# GF_Logo_PCB.net
KiCad netlist of a schematic drawn in EAGLE
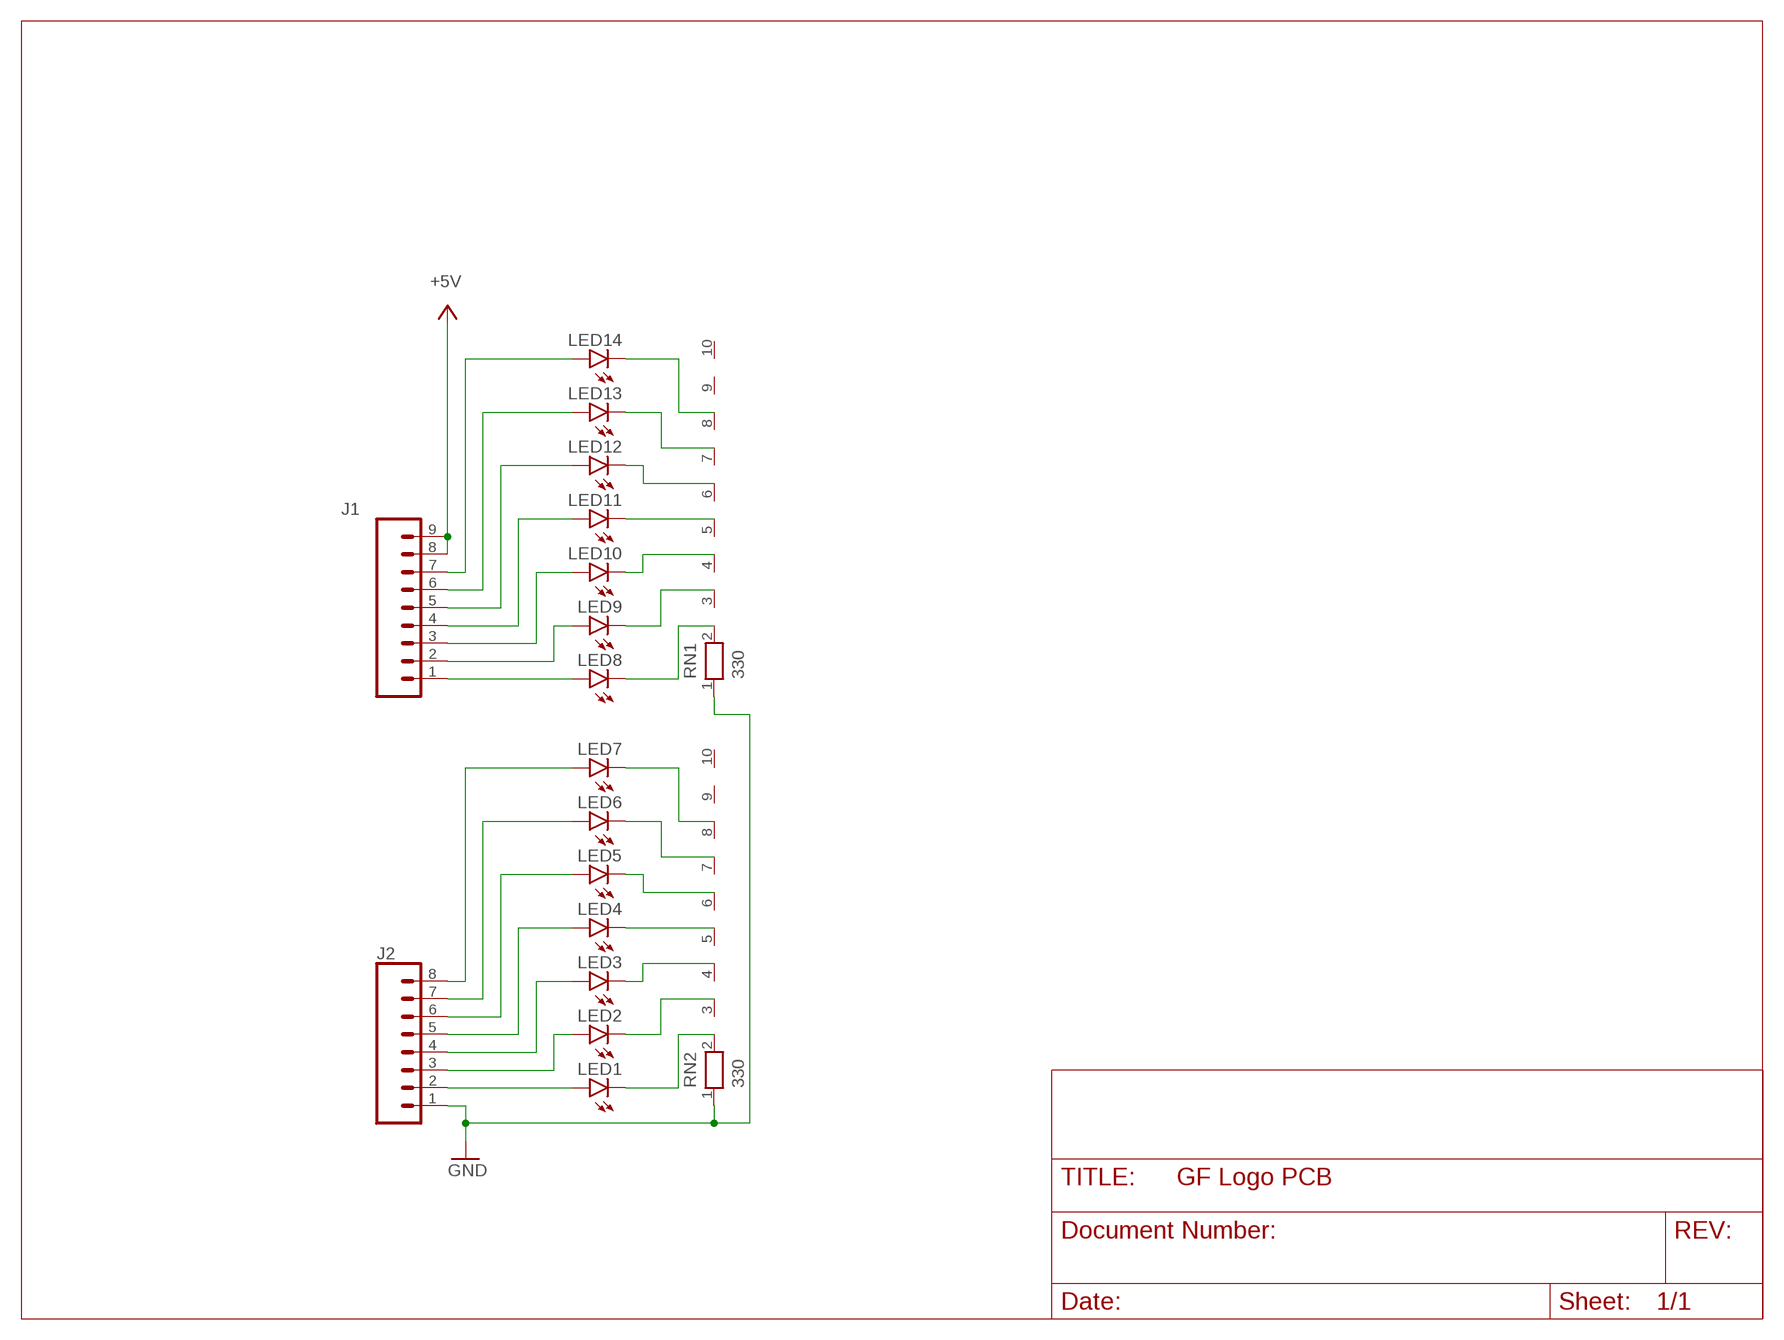
[diagram p0: schematic, sheet 1]

(export (version "E")
  (design (tool "Eeschema 10.0.6"))
  (components
    (comp (ref "J1")
      (value "CONN_09")
      (footprint "eagle-import:1X09")
      (libsource (lib "eagle-import") (part "CONN_09"))
    )
    (comp (ref "J2")
      (value "CONN_08\"")
      (footprint "eagle-import:1X08")
      (libsource (lib "eagle-import") (part "CONN_08{dblquote}"))
    )
    (comp (ref "LED1")
      (value "Grn")
      (footprint "eagle-import:LED3MM")
      (libsource (lib "eagle-import") (part "LED3MM"))
    )
    (comp (ref "LED2")
      (value "Grn")
      (footprint "eagle-import:LED3MM")
      (libsource (lib "eagle-import") (part "LED3MM"))
    )
    (comp (ref "LED3")
      (value "Grn")
      (footprint "eagle-import:LED3MM")
      (libsource (lib "eagle-import") (part "LED3MM"))
    )
    (comp (ref "LED4")
      (value "Grn")
      (footprint "eagle-import:LED3MM")
      (libsource (lib "eagle-import") (part "LED3MM"))
    )
    (comp (ref "LED5")
      (value "Grn")
      (footprint "eagle-import:LED3MM")
      (libsource (lib "eagle-import") (part "LED3MM"))
    )
    (comp (ref "LED6")
      (value "Grn")
      (footprint "eagle-import:LED3MM")
      (libsource (lib "eagle-import") (part "LED3MM"))
    )
    (comp (ref "LED7")
      (value "Grn")
      (footprint "eagle-import:LED3MM")
      (libsource (lib "eagle-import") (part "LED3MM"))
    )
    (comp (ref "LED8")
      (value "Grn")
      (footprint "eagle-import:LED3MM")
      (libsource (lib "eagle-import") (part "LED3MM"))
    )
    (comp (ref "LED9")
      (value "Grn")
      (footprint "eagle-import:LED3MM")
      (libsource (lib "eagle-import") (part "LED3MM"))
    )
    (comp (ref "LED10")
      (value "Grn")
      (footprint "eagle-import:LED3MM")
      (libsource (lib "eagle-import") (part "LED3MM"))
    )
    (comp (ref "LED11")
      (value "Grn")
      (footprint "eagle-import:LED3MM")
      (libsource (lib "eagle-import") (part "LED3MM"))
    )
    (comp (ref "LED12")
      (value "Grn")
      (footprint "eagle-import:LED3MM")
      (libsource (lib "eagle-import") (part "LED3MM"))
    )
    (comp (ref "LED13")
      (value "Grn")
      (footprint "eagle-import:LED3MM")
      (libsource (lib "eagle-import") (part "LED3MM"))
    )
    (comp (ref "LED14")
      (value "Grn")
      (footprint "eagle-import:LED3MM")
      (libsource (lib "eagle-import") (part "LED3MM"))
    )
    (comp (ref "RN1")
      (value "330")
      (footprint "eagle-import:RN-10")
      (libsource (lib "eagle-import") (part "RN09"))
    )
    (comp (ref "RN2")
      (value "330")
      (footprint "eagle-import:RN-10")
      (libsource (lib "eagle-import") (part "RN09"))
    )
  )
  (nets
    (net (code "1") (name "+5V") (class "Default")
      (node (ref "J1") (pin "8") (pinfunction "8_8") (pintype "passive"))
      (node (ref "J1") (pin "9") (pinfunction "9_9") (pintype "passive"))
    )
    (net (code "2") (name "GND") (class "Default")
      (node (ref "J2") (pin "1") (pinfunction "1_1") (pintype "passive"))
      (node (ref "RN1") (pin "1") (pinfunction "1_1") (pintype "passive"))
      (node (ref "RN2") (pin "1") (pinfunction "1_1") (pintype "passive"))
    )
    (net (code "3") (name "Net-(J1-Pad1)") (class "Default")
      (node (ref "J1") (pin "1") (pinfunction "1_1") (pintype "passive"))
      (node (ref "LED8") (pin "A") (pinfunction "A_A") (pintype "passive"))
    )
    (net (code "4") (name "Net-(J1-Pad2)") (class "Default")
      (node (ref "J1") (pin "2") (pinfunction "2_2") (pintype "passive"))
      (node (ref "LED9") (pin "A") (pinfunction "A_A") (pintype "passive"))
    )
    (net (code "5") (name "Net-(J1-Pad3)") (class "Default")
      (node (ref "J1") (pin "3") (pinfunction "3_3") (pintype "passive"))
      (node (ref "LED10") (pin "A") (pinfunction "A_A") (pintype "passive"))
    )
    (net (code "6") (name "Net-(J1-Pad4)") (class "Default")
      (node (ref "J1") (pin "4") (pinfunction "4_4") (pintype "passive"))
      (node (ref "LED11") (pin "A") (pinfunction "A_A") (pintype "passive"))
    )
    (net (code "7") (name "Net-(J1-Pad5)") (class "Default")
      (node (ref "J1") (pin "5") (pinfunction "5_5") (pintype "passive"))
      (node (ref "LED12") (pin "A") (pinfunction "A_A") (pintype "passive"))
    )
    (net (code "8") (name "Net-(J1-Pad6)") (class "Default")
      (node (ref "J1") (pin "6") (pinfunction "6_6") (pintype "passive"))
      (node (ref "LED13") (pin "A") (pinfunction "A_A") (pintype "passive"))
    )
    (net (code "9") (name "Net-(J1-Pad7)") (class "Default")
      (node (ref "J1") (pin "7") (pinfunction "7_7") (pintype "passive"))
      (node (ref "LED14") (pin "A") (pinfunction "A_A") (pintype "passive"))
    )
    (net (code "10") (name "Net-(J2-Pad2)") (class "Default")
      (node (ref "J2") (pin "2") (pinfunction "2_2") (pintype "passive"))
      (node (ref "LED1") (pin "A") (pinfunction "A_A") (pintype "passive"))
    )
    (net (code "11") (name "Net-(J2-Pad3)") (class "Default")
      (node (ref "J2") (pin "3") (pinfunction "3_3") (pintype "passive"))
      (node (ref "LED2") (pin "A") (pinfunction "A_A") (pintype "passive"))
    )
    (net (code "12") (name "Net-(J2-Pad4)") (class "Default")
      (node (ref "J2") (pin "4") (pinfunction "4_4") (pintype "passive"))
      (node (ref "LED3") (pin "A") (pinfunction "A_A") (pintype "passive"))
    )
    (net (code "13") (name "Net-(J2-Pad5)") (class "Default")
      (node (ref "J2") (pin "5") (pinfunction "5_5") (pintype "passive"))
      (node (ref "LED4") (pin "A") (pinfunction "A_A") (pintype "passive"))
    )
    (net (code "14") (name "Net-(J2-Pad6)") (class "Default")
      (node (ref "J2") (pin "6") (pinfunction "6_6") (pintype "passive"))
      (node (ref "LED5") (pin "A") (pinfunction "A_A") (pintype "passive"))
    )
    (net (code "15") (name "Net-(J2-Pad7)") (class "Default")
      (node (ref "J2") (pin "7") (pinfunction "7_7") (pintype "passive"))
      (node (ref "LED6") (pin "A") (pinfunction "A_A") (pintype "passive"))
    )
    (net (code "16") (name "Net-(J2-Pad8)") (class "Default")
      (node (ref "J2") (pin "8") (pinfunction "8_8") (pintype "passive"))
      (node (ref "LED7") (pin "A") (pinfunction "A_A") (pintype "passive"))
    )
    (net (code "17") (name "Net-(LED1-C)") (class "Default")
      (node (ref "LED1") (pin "K") (pinfunction "C_K") (pintype "passive"))
      (node (ref "RN2") (pin "2") (pinfunction "2_2") (pintype "passive"))
    )
    (net (code "18") (name "Net-(LED2-C)") (class "Default")
      (node (ref "LED2") (pin "K") (pinfunction "C_K") (pintype "passive"))
      (node (ref "RN2") (pin "3") (pinfunction "3_3") (pintype "passive"))
    )
    (net (code "19") (name "Net-(LED3-C)") (class "Default")
      (node (ref "LED3") (pin "K") (pinfunction "C_K") (pintype "passive"))
      (node (ref "RN2") (pin "4") (pinfunction "4_4") (pintype "passive"))
    )
    (net (code "20") (name "Net-(LED4-C)") (class "Default")
      (node (ref "LED4") (pin "K") (pinfunction "C_K") (pintype "passive"))
      (node (ref "RN2") (pin "5") (pinfunction "5_5") (pintype "passive"))
    )
    (net (code "21") (name "Net-(LED5-C)") (class "Default")
      (node (ref "LED5") (pin "K") (pinfunction "C_K") (pintype "passive"))
      (node (ref "RN2") (pin "6") (pinfunction "6_6") (pintype "passive"))
    )
    (net (code "22") (name "Net-(LED6-C)") (class "Default")
      (node (ref "LED6") (pin "K") (pinfunction "C_K") (pintype "passive"))
      (node (ref "RN2") (pin "7") (pinfunction "7_7") (pintype "passive"))
    )
    (net (code "23") (name "Net-(LED7-C)") (class "Default")
      (node (ref "LED7") (pin "K") (pinfunction "C_K") (pintype "passive"))
      (node (ref "RN2") (pin "8") (pinfunction "8_8") (pintype "passive"))
    )
    (net (code "24") (name "Net-(LED8-C)") (class "Default")
      (node (ref "LED8") (pin "K") (pinfunction "C_K") (pintype "passive"))
      (node (ref "RN1") (pin "2") (pinfunction "2_2") (pintype "passive"))
    )
    (net (code "25") (name "Net-(LED9-C)") (class "Default")
      (node (ref "LED9") (pin "K") (pinfunction "C_K") (pintype "passive"))
      (node (ref "RN1") (pin "3") (pinfunction "3_3") (pintype "passive"))
    )
    (net (code "26") (name "Net-(LED10-C)") (class "Default")
      (node (ref "LED10") (pin "K") (pinfunction "C_K") (pintype "passive"))
      (node (ref "RN1") (pin "4") (pinfunction "4_4") (pintype "passive"))
    )
    (net (code "27") (name "Net-(LED11-C)") (class "Default")
      (node (ref "LED11") (pin "K") (pinfunction "C_K") (pintype "passive"))
      (node (ref "RN1") (pin "5") (pinfunction "5_5") (pintype "passive"))
    )
    (net (code "28") (name "Net-(LED12-C)") (class "Default")
      (node (ref "LED12") (pin "K") (pinfunction "C_K") (pintype "passive"))
      (node (ref "RN1") (pin "6") (pinfunction "6_6") (pintype "passive"))
    )
    (net (code "29") (name "Net-(LED13-C)") (class "Default")
      (node (ref "LED13") (pin "K") (pinfunction "C_K") (pintype "passive"))
      (node (ref "RN1") (pin "7") (pinfunction "7_7") (pintype "passive"))
    )
    (net (code "30") (name "Net-(LED14-C)") (class "Default")
      (node (ref "LED14") (pin "K") (pinfunction "C_K") (pintype "passive"))
      (node (ref "RN1") (pin "8") (pinfunction "8_8") (pintype "passive"))
    )
    (net (code "31") (name "unconnected-(RN1-Pad9)") (class "Default")
      (node (ref "RN1") (pin "9") (pinfunction "9_9") (pintype "passive"))
    )
    (net (code "32") (name "unconnected-(RN1-Pad10)") (class "Default")
      (node (ref "RN1") (pin "10") (pinfunction "10_10") (pintype "passive"))
    )
    (net (code "33") (name "unconnected-(RN2-Pad9)") (class "Default")
      (node (ref "RN2") (pin "9") (pinfunction "9_9") (pintype "passive"))
    )
    (net (code "34") (name "unconnected-(RN2-Pad10)") (class "Default")
      (node (ref "RN2") (pin "10") (pinfunction "10_10") (pintype "passive"))
    )
  )
)
